# arduino-nano-dcc-v3.net
KiCad netlist of a schematic drawn in EAGLE
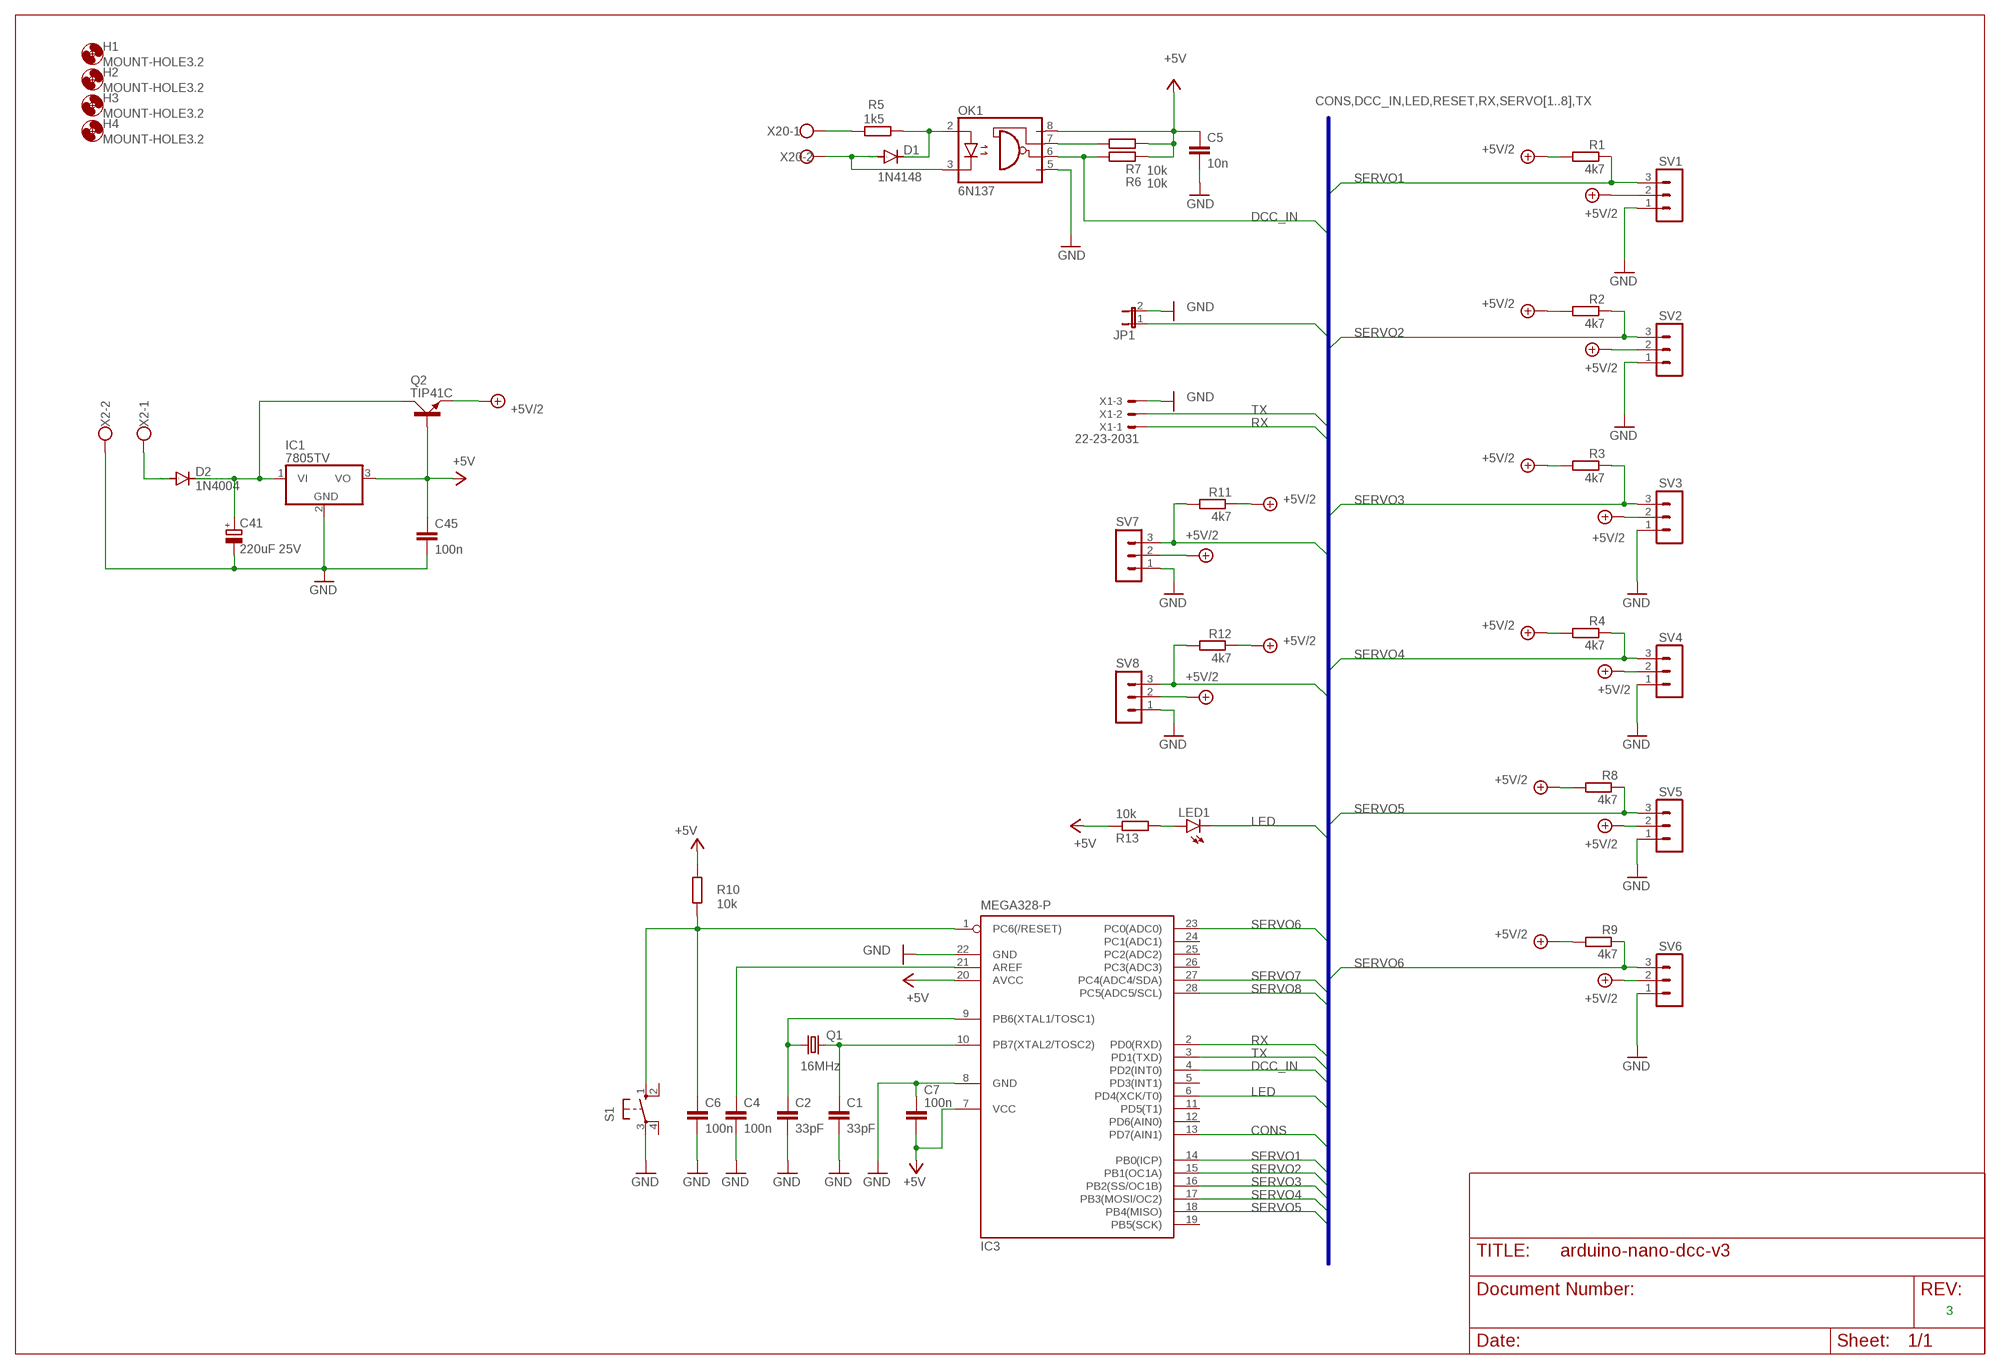
[diagram p0: schematic, sheet 1]

(export (version "E")
  (design (tool "Eeschema 10.0.6"))
  (components
    (comp (ref "C1")
      (value "33pF")
      (footprint "eagle-import:C025-024X044")
      (libsource (lib "eagle-import") (part "rcl_334_C-EU025-024X044"))
    )
    (comp (ref "C2")
      (value "33pF")
      (footprint "eagle-import:C025-024X044")
      (libsource (lib "eagle-import") (part "rcl_334_C-EU025-024X044"))
    )
    (comp (ref "C4")
      (value "100n")
      (footprint "eagle-import:C050-024X044")
      (libsource (lib "eagle-import") (part "rcl_334_C-EU050-024X044"))
    )
    (comp (ref "C5")
      (value "10n")
      (footprint "eagle-import:C050-024X044")
      (libsource (lib "eagle-import") (part "C-EU050-024X044"))
    )
    (comp (ref "C6")
      (value "100n")
      (footprint "eagle-import:C050-024X044")
      (libsource (lib "eagle-import") (part "rcl_334_C-EU050-024X044"))
    )
    (comp (ref "C7")
      (value "100n")
      (footprint "eagle-import:C050-024X044")
      (libsource (lib "eagle-import") (part "rcl_334_C-EU050-024X044"))
    )
    (comp (ref "C41")
      (value "220uF 25V")
      (footprint "eagle-import:E5-8,5")
      (libsource (lib "eagle-import") (part "CPOL-EUE5-8.5"))
    )
    (comp (ref "C45")
      (value "100n")
      (footprint "eagle-import:C050-024X044")
      (libsource (lib "eagle-import") (part "C-EU050-024X044"))
    )
    (comp (ref "D1")
      (value "1N4148")
      (footprint "eagle-import:DO35-7")
      (libsource (lib "eagle-import") (part "1N4148DO35-7"))
    )
    (comp (ref "D2")
      (value "1N4004")
      (footprint "eagle-import:DO41-10")
      (libsource (lib "eagle-import") (part "1N4004"))
    )
    (comp (ref "H1")
      (value "MOUNT-HOLE3.2")
      (footprint "eagle-import:3,2")
      (libsource (lib "eagle-import") (part "MOUNT-HOLE3.2"))
    )
    (comp (ref "H2")
      (value "MOUNT-HOLE3.2")
      (footprint "eagle-import:3,2")
      (libsource (lib "eagle-import") (part "MOUNT-HOLE3.2"))
    )
    (comp (ref "H3")
      (value "MOUNT-HOLE3.2")
      (footprint "eagle-import:3,2")
      (libsource (lib "eagle-import") (part "MOUNT-HOLE3.2"))
    )
    (comp (ref "H4")
      (value "MOUNT-HOLE3.2")
      (footprint "eagle-import:3,2")
      (libsource (lib "eagle-import") (part "MOUNT-HOLE3.2"))
    )
    (comp (ref "IC1")
      (value "7805TV")
      (footprint "eagle-import:TO220V")
      (libsource (lib "eagle-import") (part "78TV05"))
    )
    (comp (ref "IC3")
      (value "MEGA328-P")
      (footprint "eagle-import:DIL28-3")
      (libsource (lib "eagle-import") (part "MEGA8-P"))
    )
    (comp (ref "JP1")
      (value "JP1E")
      (footprint "eagle-import:JP1")
      (libsource (lib "eagle-import") (part "JP1E"))
    )
    (comp (ref "LED1")
      (value "LED3MM")
      (footprint "eagle-import:LED3MM")
      (libsource (lib "eagle-import") (part "LED3MM"))
    )
    (comp (ref "OK1")
      (value "6N137")
      (footprint "eagle-import:DIL08")
      (libsource (lib "eagle-import") (part "6N137"))
    )
    (comp (ref "Q1")
      (value "16MHz")
      (footprint "eagle-import:HC49U-V")
      (libsource (lib "eagle-import") (part "CRYSTALHC49U-V"))
    )
    (comp (ref "Q2")
      (value "TIP41C")
      (footprint "eagle-import:TO220AV")
      (libsource (lib "eagle-import") (part "TIP41C"))
    )
    (comp (ref "R1")
      (value "4k7")
      (footprint "eagle-import:0204_7")
      (libsource (lib "eagle-import") (part "R-EU_0204/7"))
    )
    (comp (ref "R2")
      (value "4k7")
      (footprint "eagle-import:0204_7")
      (libsource (lib "eagle-import") (part "R-EU_0204/7"))
    )
    (comp (ref "R3")
      (value "4k7")
      (footprint "eagle-import:0204_7")
      (libsource (lib "eagle-import") (part "R-EU_0204/7"))
    )
    (comp (ref "R4")
      (value "4k7")
      (footprint "eagle-import:0204_7")
      (libsource (lib "eagle-import") (part "R-EU_0204/7"))
    )
    (comp (ref "R5")
      (value "1k5")
      (footprint "eagle-import:0204_7")
      (libsource (lib "eagle-import") (part "R-EU_0204/7"))
    )
    (comp (ref "R6")
      (value "10k")
      (footprint "eagle-import:0204_7")
      (libsource (lib "eagle-import") (part "R-EU_0204/7"))
    )
    (comp (ref "R7")
      (value "10k")
      (footprint "eagle-import:0204_7")
      (libsource (lib "eagle-import") (part "R-EU_0204/7"))
    )
    (comp (ref "R8")
      (value "4k7")
      (footprint "eagle-import:0204_7")
      (libsource (lib "eagle-import") (part "R-EU_0204/7"))
    )
    (comp (ref "R9")
      (value "4k7")
      (footprint "eagle-import:0204_7")
      (libsource (lib "eagle-import") (part "R-EU_0204/7"))
    )
    (comp (ref "R10")
      (value "10k")
      (footprint "eagle-import:0204_7")
      (libsource (lib "eagle-import") (part "R-EU_0204/7"))
    )
    (comp (ref "R11")
      (value "4k7")
      (footprint "eagle-import:0204_7")
      (libsource (lib "eagle-import") (part "R-EU_0204/7"))
    )
    (comp (ref "R12")
      (value "4k7")
      (footprint "eagle-import:0204_5")
      (libsource (lib "eagle-import") (part "R-EU_0204/5"))
    )
    (comp (ref "R13")
      (value "10k")
      (footprint "eagle-import:0204V")
      (libsource (lib "eagle-import") (part "R-EU_0204/2V"))
    )
    (comp (ref "S1")
      (value "10-XX")
      (footprint "eagle-import:B3F-10XX")
      (fields (field (name "MPN") "B3F-1000"))
      (libsource (lib "eagle-import") (part "10-XX"))
    )
    (comp (ref "SV1")
      (value "MA03-1")
      (footprint "eagle-import:MA03-1")
      (libsource (lib "eagle-import") (part "MA03-1"))
    )
    (comp (ref "SV2")
      (value "MA03-1")
      (footprint "eagle-import:MA03-1")
      (libsource (lib "eagle-import") (part "MA03-1"))
    )
    (comp (ref "SV3")
      (value "MA03-1")
      (footprint "eagle-import:MA03-1")
      (libsource (lib "eagle-import") (part "MA03-1"))
    )
    (comp (ref "SV4")
      (value "MA03-1")
      (footprint "eagle-import:MA03-1")
      (libsource (lib "eagle-import") (part "MA03-1"))
    )
    (comp (ref "SV5")
      (value "MA03-1")
      (footprint "eagle-import:MA03-1")
      (libsource (lib "eagle-import") (part "MA03-1"))
    )
    (comp (ref "SV6")
      (value "MA03-1")
      (footprint "eagle-import:MA03-1")
      (libsource (lib "eagle-import") (part "MA03-1"))
    )
    (comp (ref "SV7")
      (value "MA03-1")
      (footprint "eagle-import:MA03-1")
      (libsource (lib "eagle-import") (part "MA03-1"))
    )
    (comp (ref "SV8")
      (value "MA03-1")
      (footprint "eagle-import:MA03-1")
      (libsource (lib "eagle-import") (part "MA03-1"))
    )
    (comp (ref "X1")
      (value "22-23-2031")
      (footprint "eagle-import:22-23-2031")
      (fields (field (name "MF") "MOLEX"))
      (libsource (lib "eagle-import") (part "22-23-2031"))
    )
    (comp (ref "X2")
      (value "W237-102")
      (footprint "eagle-import:W237-102")
      (fields (field (name "MPN") "237-102"))
      (libsource (lib "eagle-import") (part "W237-102"))
    )
    (comp (ref "X20")
      (value "W237-102")
      (footprint "eagle-import:W237-102")
      (fields (field (name "MPN") "237-102"))
      (libsource (lib "eagle-import") (part "W237-102"))
    )
  )
  (nets
    (net (code "2") (name "+5V") (class "Default")
      (node (ref "C45") (pin "1") (pinfunction "1_1") (pintype "passive"))
      (node (ref "C5") (pin "1") (pinfunction "1_1") (pintype "passive"))
      (node (ref "C7") (pin "2") (pinfunction "2_2") (pintype "passive"))
      (node (ref "IC1") (pin "3") (pinfunction "VO_3") (pintype "passive"))
      (node (ref "IC3") (pin "20") (pinfunction "AVCC_20") (pintype "power_in"))
      (node (ref "IC3") (pin "7") (pinfunction "VCC_7") (pintype "power_in"))
      (node (ref "OK1") (pin "8") (pinfunction "VCC_8") (pintype "passive"))
      (node (ref "Q2") (pin "B") (pinfunction "B_B") (pintype "passive"))
      (node (ref "R10") (pin "1") (pinfunction "1_1") (pintype "passive"))
      (node (ref "R13") (pin "1") (pinfunction "1_1") (pintype "passive"))
      (node (ref "R6") (pin "1") (pinfunction "1_1") (pintype "passive"))
      (node (ref "R7") (pin "1") (pinfunction "1_1") (pintype "passive"))
    )
    (net (code "3") (name "+5V{slash}2") (class "Default")
      (node (ref "Q2") (pin "E") (pinfunction "E_E") (pintype "passive"))
      (node (ref "R1") (pin "2") (pinfunction "2_2") (pintype "passive"))
      (node (ref "R11") (pin "1") (pinfunction "1_1") (pintype "passive"))
      (node (ref "R12") (pin "1") (pinfunction "1_1") (pintype "passive"))
      (node (ref "R2") (pin "2") (pinfunction "2_2") (pintype "passive"))
      (node (ref "R3") (pin "2") (pinfunction "2_2") (pintype "passive"))
      (node (ref "R4") (pin "2") (pinfunction "2_2") (pintype "passive"))
      (node (ref "R8") (pin "2") (pinfunction "2_2") (pintype "passive"))
      (node (ref "R9") (pin "2") (pinfunction "2_2") (pintype "passive"))
      (node (ref "SV1") (pin "2") (pinfunction "2_2") (pintype "passive"))
      (node (ref "SV2") (pin "2") (pinfunction "2_2") (pintype "passive"))
      (node (ref "SV3") (pin "2") (pinfunction "2_2") (pintype "passive"))
      (node (ref "SV4") (pin "2") (pinfunction "2_2") (pintype "passive"))
      (node (ref "SV5") (pin "2") (pinfunction "2_2") (pintype "passive"))
      (node (ref "SV6") (pin "2") (pinfunction "2_2") (pintype "passive"))
      (node (ref "SV7") (pin "2") (pinfunction "2_2") (pintype "passive"))
      (node (ref "SV8") (pin "2") (pinfunction "2_2") (pintype "passive"))
    )
    (net (code "4") (name "/CONS") (class "Default")
      (node (ref "IC3") (pin "13") (pinfunction "PD7(AIN1)_13") (pintype "bidirectional"))
      (node (ref "JP1") (pin "1") (pinfunction "1_1") (pintype "passive"))
    )
    (net (code "5") (name "/DCC_IN") (class "Default")
      (node (ref "IC3") (pin "4") (pinfunction "PD2(INT0)_4") (pintype "bidirectional"))
      (node (ref "OK1") (pin "6") (pinfunction "VO_6") (pintype "passive"))
      (node (ref "R7") (pin "2") (pinfunction "2_2") (pintype "passive"))
    )
    (net (code "6") (name "/LED") (class "Default")
      (node (ref "IC3") (pin "6") (pinfunction "PD4(XCK/T0)_6") (pintype "bidirectional"))
      (node (ref "LED1") (pin "K") (pinfunction "C_K") (pintype "passive"))
    )
    (net (code "7") (name "/RX") (class "Default")
      (node (ref "IC3") (pin "2") (pinfunction "PD0(RXD)_2") (pintype "bidirectional"))
      (node (ref "X1") (pin "1") (pinfunction "S_1") (pintype "passive"))
    )
    (net (code "8") (name "/SERVO1") (class "Default")
      (node (ref "IC3") (pin "14") (pinfunction "PB0(ICP)_14") (pintype "bidirectional"))
      (node (ref "R1") (pin "1") (pinfunction "1_1") (pintype "passive"))
      (node (ref "SV1") (pin "3") (pinfunction "3_3") (pintype "passive"))
    )
    (net (code "9") (name "/SERVO2") (class "Default")
      (node (ref "IC3") (pin "15") (pinfunction "PB1(OC1A)_15") (pintype "bidirectional"))
      (node (ref "R2") (pin "1") (pinfunction "1_1") (pintype "passive"))
      (node (ref "SV2") (pin "3") (pinfunction "3_3") (pintype "passive"))
    )
    (net (code "10") (name "/SERVO3") (class "Default")
      (node (ref "IC3") (pin "16") (pinfunction "PB2(SS/OC1B)_16") (pintype "bidirectional"))
      (node (ref "R3") (pin "1") (pinfunction "1_1") (pintype "passive"))
      (node (ref "SV3") (pin "3") (pinfunction "3_3") (pintype "passive"))
    )
    (net (code "11") (name "/SERVO4") (class "Default")
      (node (ref "IC3") (pin "17") (pinfunction "PB3(MOSI/OC2)_17") (pintype "bidirectional"))
      (node (ref "R4") (pin "1") (pinfunction "1_1") (pintype "passive"))
      (node (ref "SV4") (pin "3") (pinfunction "3_3") (pintype "passive"))
    )
    (net (code "12") (name "/SERVO5") (class "Default")
      (node (ref "IC3") (pin "18") (pinfunction "PB4(MISO)_18") (pintype "bidirectional"))
      (node (ref "R8") (pin "1") (pinfunction "1_1") (pintype "passive"))
      (node (ref "SV5") (pin "3") (pinfunction "3_3") (pintype "passive"))
    )
    (net (code "13") (name "/SERVO6") (class "Default")
      (node (ref "IC3") (pin "23") (pinfunction "PC0(ADC0)_23") (pintype "bidirectional"))
      (node (ref "R9") (pin "1") (pinfunction "1_1") (pintype "passive"))
      (node (ref "SV6") (pin "3") (pinfunction "3_3") (pintype "passive"))
    )
    (net (code "14") (name "/SERVO7") (class "Default")
      (node (ref "IC3") (pin "27") (pinfunction "PC4(ADC4/SDA)_27") (pintype "bidirectional"))
      (node (ref "R11") (pin "2") (pinfunction "2_2") (pintype "passive"))
      (node (ref "SV7") (pin "3") (pinfunction "3_3") (pintype "passive"))
    )
    (net (code "15") (name "/SERVO8") (class "Default")
      (node (ref "IC3") (pin "28") (pinfunction "PC5(ADC5/SCL)_28") (pintype "bidirectional"))
      (node (ref "R12") (pin "2") (pinfunction "2_2") (pintype "passive"))
      (node (ref "SV8") (pin "3") (pinfunction "3_3") (pintype "passive"))
    )
    (net (code "16") (name "/TX") (class "Default")
      (node (ref "IC3") (pin "3") (pinfunction "PD1(TXD)_3") (pintype "bidirectional"))
      (node (ref "X1") (pin "2") (pinfunction "S_2") (pintype "passive"))
    )
    (net (code "18") (name "GND") (class "Default")
      (node (ref "C1") (pin "2") (pinfunction "2_2") (pintype "passive"))
      (node (ref "C2") (pin "2") (pinfunction "2_2") (pintype "passive"))
      (node (ref "C4") (pin "2") (pinfunction "2_2") (pintype "passive"))
      (node (ref "C41") (pin "-") (pinfunction "-_-") (pintype "passive"))
      (node (ref "C45") (pin "2") (pinfunction "2_2") (pintype "passive"))
      (node (ref "C5") (pin "2") (pinfunction "2_2") (pintype "passive"))
      (node (ref "C6") (pin "2") (pinfunction "2_2") (pintype "passive"))
      (node (ref "C7") (pin "1") (pinfunction "1_1") (pintype "passive"))
      (node (ref "IC1") (pin "2") (pinfunction "GND_2") (pintype "passive"))
      (node (ref "IC3") (pin "22") (pinfunction "GND_22") (pintype "power_in"))
      (node (ref "IC3") (pin "8") (pinfunction "GND_8") (pintype "power_in"))
      (node (ref "JP1") (pin "2") (pinfunction "2_2") (pintype "passive"))
      (node (ref "OK1") (pin "5") (pinfunction "GND_5") (pintype "passive"))
      (node (ref "S1") (pin "3") (pinfunction "P_3") (pintype "passive"))
      (node (ref "SV1") (pin "1") (pinfunction "1_1") (pintype "passive"))
      (node (ref "SV2") (pin "1") (pinfunction "1_1") (pintype "passive"))
      (node (ref "SV3") (pin "1") (pinfunction "1_1") (pintype "passive"))
      (node (ref "SV4") (pin "1") (pinfunction "1_1") (pintype "passive"))
      (node (ref "SV5") (pin "1") (pinfunction "1_1") (pintype "passive"))
      (node (ref "SV6") (pin "1") (pinfunction "1_1") (pintype "passive"))
      (node (ref "SV7") (pin "1") (pinfunction "1_1") (pintype "passive"))
      (node (ref "SV8") (pin "1") (pinfunction "1_1") (pintype "passive"))
      (node (ref "X1") (pin "3") (pinfunction "S_3") (pintype "passive"))
      (node (ref "X2") (pin "2") (pinfunction "KL_2") (pintype "passive"))
    )
    (net (code "19") (name "Net-(IC1-VI)") (class "Default")
      (node (ref "C41") (pin "+") (pinfunction "+_+") (pintype "passive"))
      (node (ref "D2") (pin "C") (pinfunction "C_C") (pintype "passive"))
      (node (ref "IC1") (pin "1") (pinfunction "VI_1") (pintype "input"))
      (node (ref "Q2") (pin "C") (pinfunction "C_C") (pintype "passive"))
    )
    (net (code "20") (name "Net-(IC3-AREF)") (class "Default")
      (node (ref "C4") (pin "1") (pinfunction "1_1") (pintype "passive"))
      (node (ref "IC3") (pin "21") (pinfunction "AREF_21") (pintype "passive"))
    )
    (net (code "21") (name "Net-(IC3-PB6(XTAL1{slash}TOSC1))") (class "Default")
      (node (ref "C2") (pin "1") (pinfunction "1_1") (pintype "passive"))
      (node (ref "IC3") (pin "9") (pinfunction "PB6(XTAL1/TOSC1)_9") (pintype "bidirectional"))
      (node (ref "Q1") (pin "1") (pinfunction "1_1") (pintype "passive"))
    )
    (net (code "22") (name "Net-(IC3-PB7(XTAL2{slash}TOSC2))") (class "Default")
      (node (ref "C1") (pin "1") (pinfunction "1_1") (pintype "passive"))
      (node (ref "IC3") (pin "10") (pinfunction "PB7(XTAL2/TOSC2)_10") (pintype "bidirectional"))
      (node (ref "Q1") (pin "2") (pinfunction "2_2") (pintype "passive"))
    )
    (net (code "23") (name "Net-(IC3-PC6({slash}RESET))") (class "Default")
      (node (ref "C6") (pin "1") (pinfunction "1_1") (pintype "passive"))
      (node (ref "IC3") (pin "1") (pinfunction "PC6(/RESET)_1") (pintype "bidirectional"))
      (node (ref "R10") (pin "2") (pinfunction "2_2") (pintype "passive"))
      (node (ref "S1") (pin "1") (pinfunction "S_1") (pintype "passive"))
    )
    (net (code "24") (name "Net-(LED1-PadA)") (class "Default")
      (node (ref "LED1") (pin "A") (pinfunction "A_A") (pintype "passive"))
      (node (ref "R13") (pin "2") (pinfunction "2_2") (pintype "passive"))
    )
    (net (code "25") (name "Net-(OK1-A)") (class "Default")
      (node (ref "D1") (pin "C") (pinfunction "C_C") (pintype "passive"))
      (node (ref "OK1") (pin "2") (pinfunction "A_2") (pintype "passive"))
      (node (ref "R5") (pin "1") (pinfunction "1_1") (pintype "passive"))
    )
    (net (code "26") (name "Net-(OK1-C)") (class "Default")
      (node (ref "D1") (pin "A") (pinfunction "A_A") (pintype "passive"))
      (node (ref "OK1") (pin "3") (pinfunction "C_3") (pintype "passive"))
      (node (ref "X20") (pin "2") (pinfunction "KL_2") (pintype "passive"))
    )
    (net (code "27") (name "Net-(OK1-VE)") (class "Default")
      (node (ref "OK1") (pin "7") (pinfunction "VE_7") (pintype "passive"))
      (node (ref "R6") (pin "2") (pinfunction "2_2") (pintype "passive"))
    )
    (net (code "28") (name "Net-(X2A-KL)") (class "Default")
      (node (ref "D2") (pin "A") (pinfunction "A_A") (pintype "passive"))
      (node (ref "X2") (pin "1") (pinfunction "KL_1") (pintype "passive"))
    )
    (net (code "29") (name "Net-(X20A-KL)") (class "Default")
      (node (ref "R5") (pin "2") (pinfunction "2_2") (pintype "passive"))
      (node (ref "X20") (pin "1") (pinfunction "KL_1") (pintype "passive"))
    )
    (net (code "30") (name "unconnected-(IC3-PB5(SCK)-Pad19)") (class "Default")
      (node (ref "IC3") (pin "19") (pinfunction "PB5(SCK)_19") (pintype "bidirectional"))
    )
    (net (code "31") (name "unconnected-(IC3-PC1(ADC1)-Pad24)") (class "Default")
      (node (ref "IC3") (pin "24") (pinfunction "PC1(ADC1)_24") (pintype "bidirectional"))
    )
    (net (code "32") (name "unconnected-(IC3-PC2(ADC2)-Pad25)") (class "Default")
      (node (ref "IC3") (pin "25") (pinfunction "PC2(ADC2)_25") (pintype "bidirectional"))
    )
    (net (code "33") (name "unconnected-(IC3-PC3(ADC3)-Pad26)") (class "Default")
      (node (ref "IC3") (pin "26") (pinfunction "PC3(ADC3)_26") (pintype "bidirectional"))
    )
    (net (code "34") (name "unconnected-(IC3-PD3(INT1)-Pad5)") (class "Default")
      (node (ref "IC3") (pin "5") (pinfunction "PD3(INT1)_5") (pintype "bidirectional"))
    )
    (net (code "35") (name "unconnected-(IC3-PD5(T1)-Pad11)") (class "Default")
      (node (ref "IC3") (pin "11") (pinfunction "PD5(T1)_11") (pintype "bidirectional"))
    )
    (net (code "36") (name "unconnected-(IC3-PD6(AIN0)-Pad12)") (class "Default")
      (node (ref "IC3") (pin "12") (pinfunction "PD6(AIN0)_12") (pintype "bidirectional"))
    )
    (net (code "37") (name "unconnected-(S1-P1-Pad4)") (class "Default")
      (node (ref "S1") (pin "4") (pinfunction "P1_4") (pintype "passive"))
    )
    (net (code "38") (name "unconnected-(S1-S1-Pad2)") (class "Default")
      (node (ref "S1") (pin "2") (pinfunction "S1_2") (pintype "passive"))
    )
  )
)
